# buck.net
KiCad netlist of a schematic drawn in EAGLE
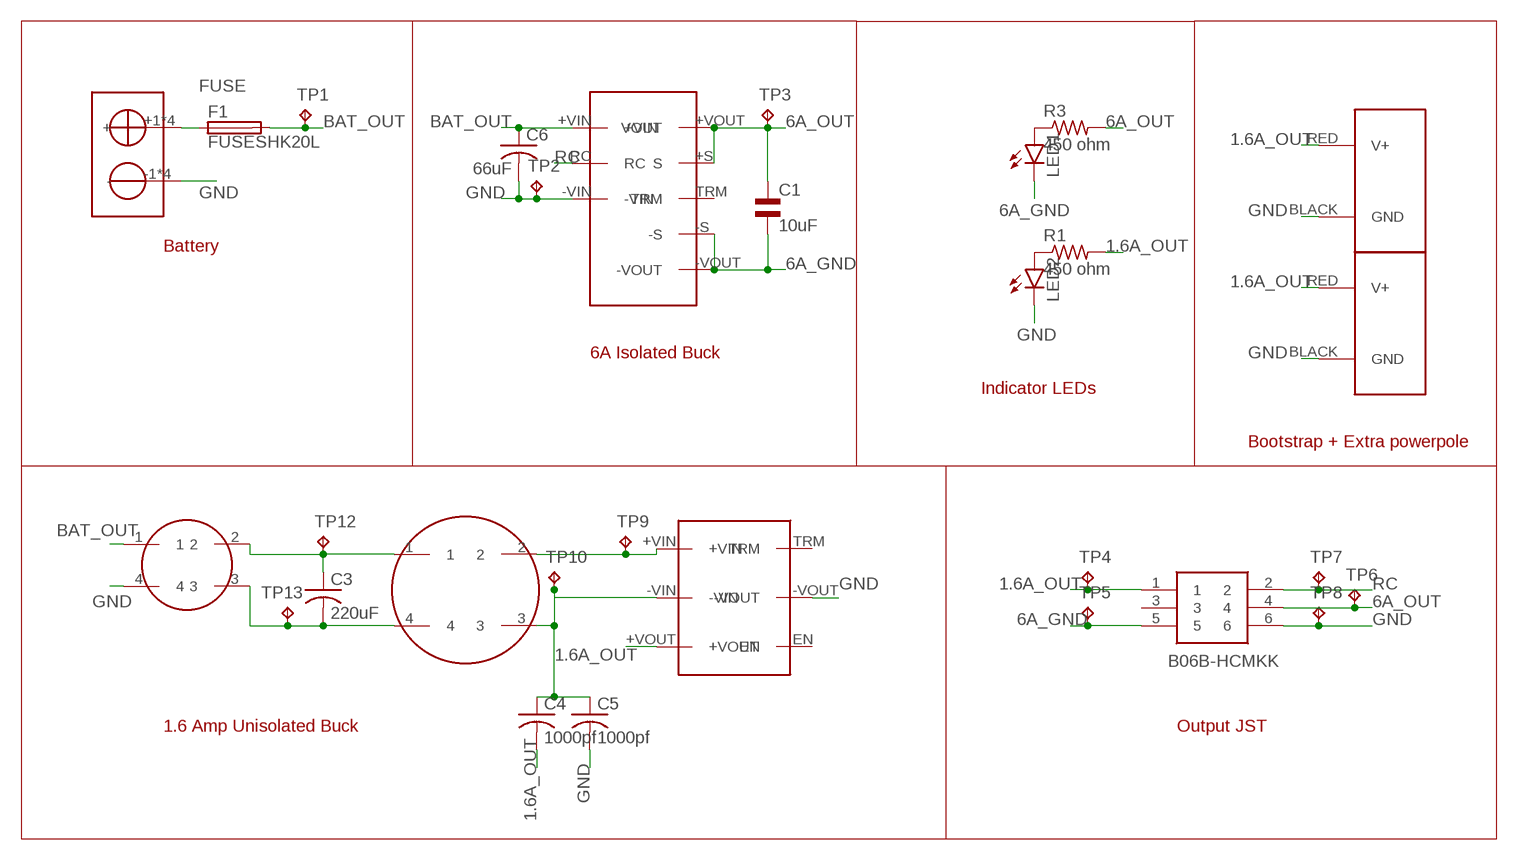
[diagram p0: schematic, sheet 1]

(export (version "E")
  (design (tool "Eeschema 10.0.6"))
  (components
    (comp (ref "BUCK150UH")
      (value "CMNMODECHOKE150UH")
      (footprint "eagle-import:CMNMODECHOKE150UH")
      (libsource (lib "eagle-import") (part "CMNMODECHOKE150UH"))
    )
    (comp (ref "C1")
      (value "10uF")
      (footprint "eagle-import:EU25-10")
      (libsource (lib "eagle-import") (part "EL-BI25-10AXIAL"))
    )
    (comp (ref "C3")
      (value "220uF")
      (footprint "eagle-import:C0805")
      (libsource (lib "eagle-import") (part "C-USC0805"))
    )
    (comp (ref "C4")
      (value "1000pf")
      (footprint "eagle-import:C0805")
      (libsource (lib "eagle-import") (part "C-USC0805"))
    )
    (comp (ref "C5")
      (value "1000pf")
      (footprint "eagle-import:C0805")
      (libsource (lib "eagle-import") (part "C-USC0805"))
    )
    (comp (ref "C6")
      (value "66uF")
      (footprint "eagle-import:C0805")
      (libsource (lib "eagle-import") (part "C-USC0805"))
    )
    (comp (ref "CHOKEME")
      (value "CMNMODECHOKE1.2MH")
      (footprint "eagle-import:CMNMODECHOKE1.2MH")
      (libsource (lib "eagle-import") (part "CMNMODECHOKE1.2MH"))
    )
    (comp (ref "F1")
      (value "FUSESHK20L")
      (footprint "eagle-import:SHK20L")
      (libsource (lib "eagle-import") (part "FUSESHK20L"))
    )
    (comp (ref "J1")
      (value "B06B-HCMKK")
      (footprint "eagle-import:B06BHCMKK")
      (fields (field (name "MOUSER_PART_NUMBER") "306-B06B-HCMKK"))
      (libsource (lib "eagle-import") (part "B06B-HCMKK"))
    )
    (comp (ref "J2")
      (value "POWERPOLE_POWER45A_DRILL")
      (footprint "eagle-import:POWERPOLE_PAIR_45A_HOLE")
      (libsource (lib "eagle-import") (part "POWERPOLE_POWER45A_DRILL"))
    )
    (comp (ref "J3")
      (value "POWERPOLE_POWER45A_DRILL")
      (footprint "eagle-import:POWERPOLE_PAIR_45A_HOLE")
      (libsource (lib "eagle-import") (part "POWERPOLE_POWER45A_DRILL"))
    )
    (comp (ref "LED1")
      (value "LEDCHIP-LED0603")
      (footprint "eagle-import:CHIP-LED0603")
      (libsource (lib "eagle-import") (part "LEDCHIP-LED0603"))
    )
    (comp (ref "LED2")
      (value "LEDCHIP-LED0603")
      (footprint "eagle-import:CHIP-LED0603")
      (libsource (lib "eagle-import") (part "LEDCHIP-LED0603"))
    )
    (comp (ref "R1")
      (value "450 ohm")
      (footprint "eagle-import:R0805")
      (libsource (lib "eagle-import") (part "R-US_R0805"))
    )
    (comp (ref "R3")
      (value "450 ohm")
      (footprint "eagle-import:R0805")
      (libsource (lib "eagle-import") (part "R-US_R0805"))
    )
    (comp (ref "TP1")
      (value "TPPAD1-13")
      (footprint "eagle-import:P1-13")
      (libsource (lib "eagle-import") (part "TPPAD1-13"))
    )
    (comp (ref "TP2")
      (value "TPPAD1-13")
      (footprint "eagle-import:P1-13")
      (libsource (lib "eagle-import") (part "TPPAD1-13"))
    )
    (comp (ref "TP3")
      (value "TPPAD1-13")
      (footprint "eagle-import:P1-13")
      (libsource (lib "eagle-import") (part "TPPAD1-13"))
    )
    (comp (ref "TP4")
      (value "TPPAD1-13")
      (footprint "eagle-import:P1-13")
      (libsource (lib "eagle-import") (part "TPPAD1-13"))
    )
    (comp (ref "TP5")
      (value "TPPAD1-13")
      (footprint "eagle-import:P1-13")
      (libsource (lib "eagle-import") (part "TPPAD1-13"))
    )
    (comp (ref "TP6")
      (value "TPPAD1-13")
      (footprint "eagle-import:P1-13")
      (libsource (lib "eagle-import") (part "TPPAD1-13"))
    )
    (comp (ref "TP7")
      (value "TPPAD1-13")
      (footprint "eagle-import:P1-13")
      (libsource (lib "eagle-import") (part "TPPAD1-13"))
    )
    (comp (ref "TP8")
      (value "TPPAD1-13")
      (footprint "eagle-import:P1-13")
      (libsource (lib "eagle-import") (part "TPPAD1-13"))
    )
    (comp (ref "TP9")
      (value "TPPAD1-13")
      (footprint "eagle-import:P1-13")
      (libsource (lib "eagle-import") (part "TPPAD1-13"))
    )
    (comp (ref "TP10")
      (value "TPPAD1-13")
      (footprint "eagle-import:P1-13")
      (libsource (lib "eagle-import") (part "TPPAD1-13"))
    )
    (comp (ref "TP12")
      (value "TPPAD1-13")
      (footprint "eagle-import:P1-13")
      (libsource (lib "eagle-import") (part "TPPAD1-13"))
    )
    (comp (ref "TP13")
      (value "TPPAD1-13")
      (footprint "eagle-import:P1-13")
      (libsource (lib "eagle-import") (part "TPPAD1-13"))
    )
    (comp (ref "U$1")
      (value "12V6ABUCKCONVERTER")
      (footprint "eagle-import:12V6ABUCKCONVERTER")
      (libsource (lib "eagle-import") (part "12V6ABUCKCONVERTER"))
    )
    (comp (ref "U$2")
      (value "SB50")
      (footprint "eagle-import:MINI-SB-50")
      (libsource (lib "eagle-import") (part "SB50"))
    )
    (comp (ref "U$3")
      (value "BUCK1.6A")
      (footprint "eagle-import:BUCK1.6A")
      (libsource (lib "eagle-import") (part "BUCK1.6A"))
    )
  )
  (nets
    (net (code "1") (name "/1.6A_OUT") (class "Default")
      (node (ref "C4") (pin "2") (pinfunction "2_2") (pintype "passive"))
      (node (ref "J1") (pin "1") (pinfunction "1_1") (pintype "bidirectional"))
      (node (ref "J2") (pin "RED") (pinfunction "V+_RED") (pintype "power_in"))
      (node (ref "J3") (pin "RED") (pinfunction "V+_RED") (pintype "power_in"))
      (node (ref "R1") (pin "2") (pinfunction "2_2") (pintype "passive"))
      (node (ref "TP4") (pin "TP") (pinfunction "TP_TP") (pintype "input"))
      (node (ref "U$3") (pin "+VOUT") (pinfunction "+VOUT_+VOUT") (pintype "bidirectional"))
    )
    (net (code "2") (name "/6A_GND") (class "Default")
      (node (ref "C1") (pin "2") (pinfunction "2_2") (pintype "passive"))
      (node (ref "J1") (pin "5") (pinfunction "5_5") (pintype "bidirectional"))
      (node (ref "LED1") (pin "C") (pinfunction "C_C") (pintype "passive"))
      (node (ref "TP5") (pin "TP") (pinfunction "TP_TP") (pintype "input"))
      (node (ref "U$1") (pin "-S") (pinfunction "-S_-S") (pintype "bidirectional"))
      (node (ref "U$1") (pin "-VOUT") (pinfunction "-VOUT_-VOUT") (pintype "bidirectional"))
    )
    (net (code "3") (name "/6A_OUT") (class "Default")
      (node (ref "C1") (pin "1") (pinfunction "1_1") (pintype "passive"))
      (node (ref "J1") (pin "4") (pinfunction "4_4") (pintype "bidirectional"))
      (node (ref "R3") (pin "2") (pinfunction "2_2") (pintype "passive"))
      (node (ref "TP3") (pin "TP") (pinfunction "TP_TP") (pintype "input"))
      (node (ref "TP6") (pin "TP") (pinfunction "TP_TP") (pintype "input"))
      (node (ref "U$1") (pin "+S") (pinfunction "S_+S") (pintype "bidirectional"))
      (node (ref "U$1") (pin "+VOUT") (pinfunction "VOUT_+VOUT") (pintype "bidirectional"))
    )
    (net (code "4") (name "/BAT_OUT") (class "Default")
      (node (ref "BUCK150UH") (pin "1") (pinfunction "1_1") (pintype "bidirectional"))
      (node (ref "C6") (pin "1") (pinfunction "1_1") (pintype "passive"))
      (node (ref "F1") (pin "2A") (pinfunction "2_2A") (pintype "passive"))
      (node (ref "TP1") (pin "TP") (pinfunction "TP_TP") (pintype "input"))
      (node (ref "U$1") (pin "+VIN") (pinfunction "+VIN_+VIN") (pintype "bidirectional"))
    )
    (net (code "5") (name "/FUSE") (class "Default")
      (node (ref "F1") (pin "1A") (pinfunction "1_1A") (pintype "passive"))
      (node (ref "U$2") (pin "+1") (pinfunction "+_+1") (pintype "bidirectional"))
      (node (ref "U$2") (pin "+2") (pinfunction "+_+2") (pintype "bidirectional"))
      (node (ref "U$2") (pin "+3") (pinfunction "+_+3") (pintype "bidirectional"))
      (node (ref "U$2") (pin "+4") (pinfunction "+_+4") (pintype "bidirectional"))
    )
    (net (code "6") (name "/GND") (class "Default")
      (node (ref "BUCK150UH") (pin "4") (pinfunction "4_4") (pintype "bidirectional"))
      (node (ref "C5") (pin "2") (pinfunction "2_2") (pintype "passive"))
      (node (ref "C6") (pin "2") (pinfunction "2_2") (pintype "passive"))
      (node (ref "J1") (pin "6") (pinfunction "6_6") (pintype "bidirectional"))
      (node (ref "J2") (pin "BLACK") (pinfunction "GND_BLACK") (pintype "power_in"))
      (node (ref "J3") (pin "BLACK") (pinfunction "GND_BLACK") (pintype "power_in"))
      (node (ref "LED2") (pin "C") (pinfunction "C_C") (pintype "passive"))
      (node (ref "TP2") (pin "TP") (pinfunction "TP_TP") (pintype "input"))
      (node (ref "TP8") (pin "TP") (pinfunction "TP_TP") (pintype "input"))
      (node (ref "U$1") (pin "-VIN") (pinfunction "-VIN_-VIN") (pintype "bidirectional"))
      (node (ref "U$2") (pin "-1") (pinfunction "-_-1") (pintype "bidirectional"))
      (node (ref "U$2") (pin "-2") (pinfunction "-_-2") (pintype "bidirectional"))
      (node (ref "U$2") (pin "-3") (pinfunction "-_-3") (pintype "bidirectional"))
      (node (ref "U$2") (pin "-4") (pinfunction "-_-4") (pintype "bidirectional"))
      (node (ref "U$3") (pin "-VOUT") (pinfunction "-VOUT_-VOUT") (pintype "bidirectional"))
    )
    (net (code "7") (name "/RC") (class "Default")
      (node (ref "J1") (pin "2") (pinfunction "2_2") (pintype "bidirectional"))
      (node (ref "TP7") (pin "TP") (pinfunction "TP_TP") (pintype "input"))
      (node (ref "U$1") (pin "RC") (pinfunction "RC_RC") (pintype "bidirectional"))
    )
    (net (code "8") (name "Net-(BUCK150UH-Pad2)") (class "Default")
      (node (ref "BUCK150UH") (pin "2") (pinfunction "2_2") (pintype "bidirectional"))
      (node (ref "C3") (pin "1") (pinfunction "1_1") (pintype "passive"))
      (node (ref "CHOKEME") (pin "1") (pinfunction "1_1") (pintype "bidirectional"))
      (node (ref "TP12") (pin "TP") (pinfunction "TP_TP") (pintype "input"))
    )
    (net (code "9") (name "Net-(BUCK150UH-Pad3)") (class "Default")
      (node (ref "BUCK150UH") (pin "3") (pinfunction "3_3") (pintype "bidirectional"))
      (node (ref "C3") (pin "2") (pinfunction "2_2") (pintype "passive"))
      (node (ref "CHOKEME") (pin "4") (pinfunction "4_4") (pintype "bidirectional"))
      (node (ref "TP13") (pin "TP") (pinfunction "TP_TP") (pintype "input"))
    )
    (net (code "10") (name "Net-(C4-Pad1)") (class "Default")
      (node (ref "C4") (pin "1") (pinfunction "1_1") (pintype "passive"))
      (node (ref "C5") (pin "1") (pinfunction "1_1") (pintype "passive"))
      (node (ref "CHOKEME") (pin "3") (pinfunction "3_3") (pintype "bidirectional"))
      (node (ref "TP10") (pin "TP") (pinfunction "TP_TP") (pintype "input"))
      (node (ref "U$3") (pin "-VIN") (pinfunction "-VIN_-VIN") (pintype "bidirectional"))
    )
    (net (code "11") (name "Net-(CHOKEME-Pad2)") (class "Default")
      (node (ref "CHOKEME") (pin "2") (pinfunction "2_2") (pintype "bidirectional"))
      (node (ref "TP9") (pin "TP") (pinfunction "TP_TP") (pintype "input"))
      (node (ref "U$3") (pin "+VIN") (pinfunction "+VIN_+VIN") (pintype "bidirectional"))
    )
    (net (code "12") (name "Net-(LED1-PadA)") (class "Default")
      (node (ref "LED1") (pin "A") (pinfunction "A_A") (pintype "passive"))
      (node (ref "R3") (pin "1") (pinfunction "1_1") (pintype "passive"))
    )
    (net (code "13") (name "Net-(LED2-PadA)") (class "Default")
      (node (ref "LED2") (pin "A") (pinfunction "A_A") (pintype "passive"))
      (node (ref "R1") (pin "1") (pinfunction "1_1") (pintype "passive"))
    )
    (net (code "14") (name "unconnected-(J1-Pad3)") (class "Default")
      (node (ref "J1") (pin "3") (pinfunction "3_3") (pintype "bidirectional"))
    )
    (net (code "15") (name "unconnected-(U$1-PadTRM)") (class "Default")
      (node (ref "U$1") (pin "TRM") (pinfunction "TRM_TRM") (pintype "bidirectional"))
    )
    (net (code "16") (name "unconnected-(U$3-PadEN)") (class "Default")
      (node (ref "U$3") (pin "EN") (pinfunction "EN_EN") (pintype "bidirectional"))
    )
    (net (code "17") (name "unconnected-(U$3-PadTRM)") (class "Default")
      (node (ref "U$3") (pin "TRM") (pinfunction "TRM_TRM") (pintype "bidirectional"))
    )
  )
)
